# 1_Interface.net
KiCad netlist of a schematic drawn in Altium Designer
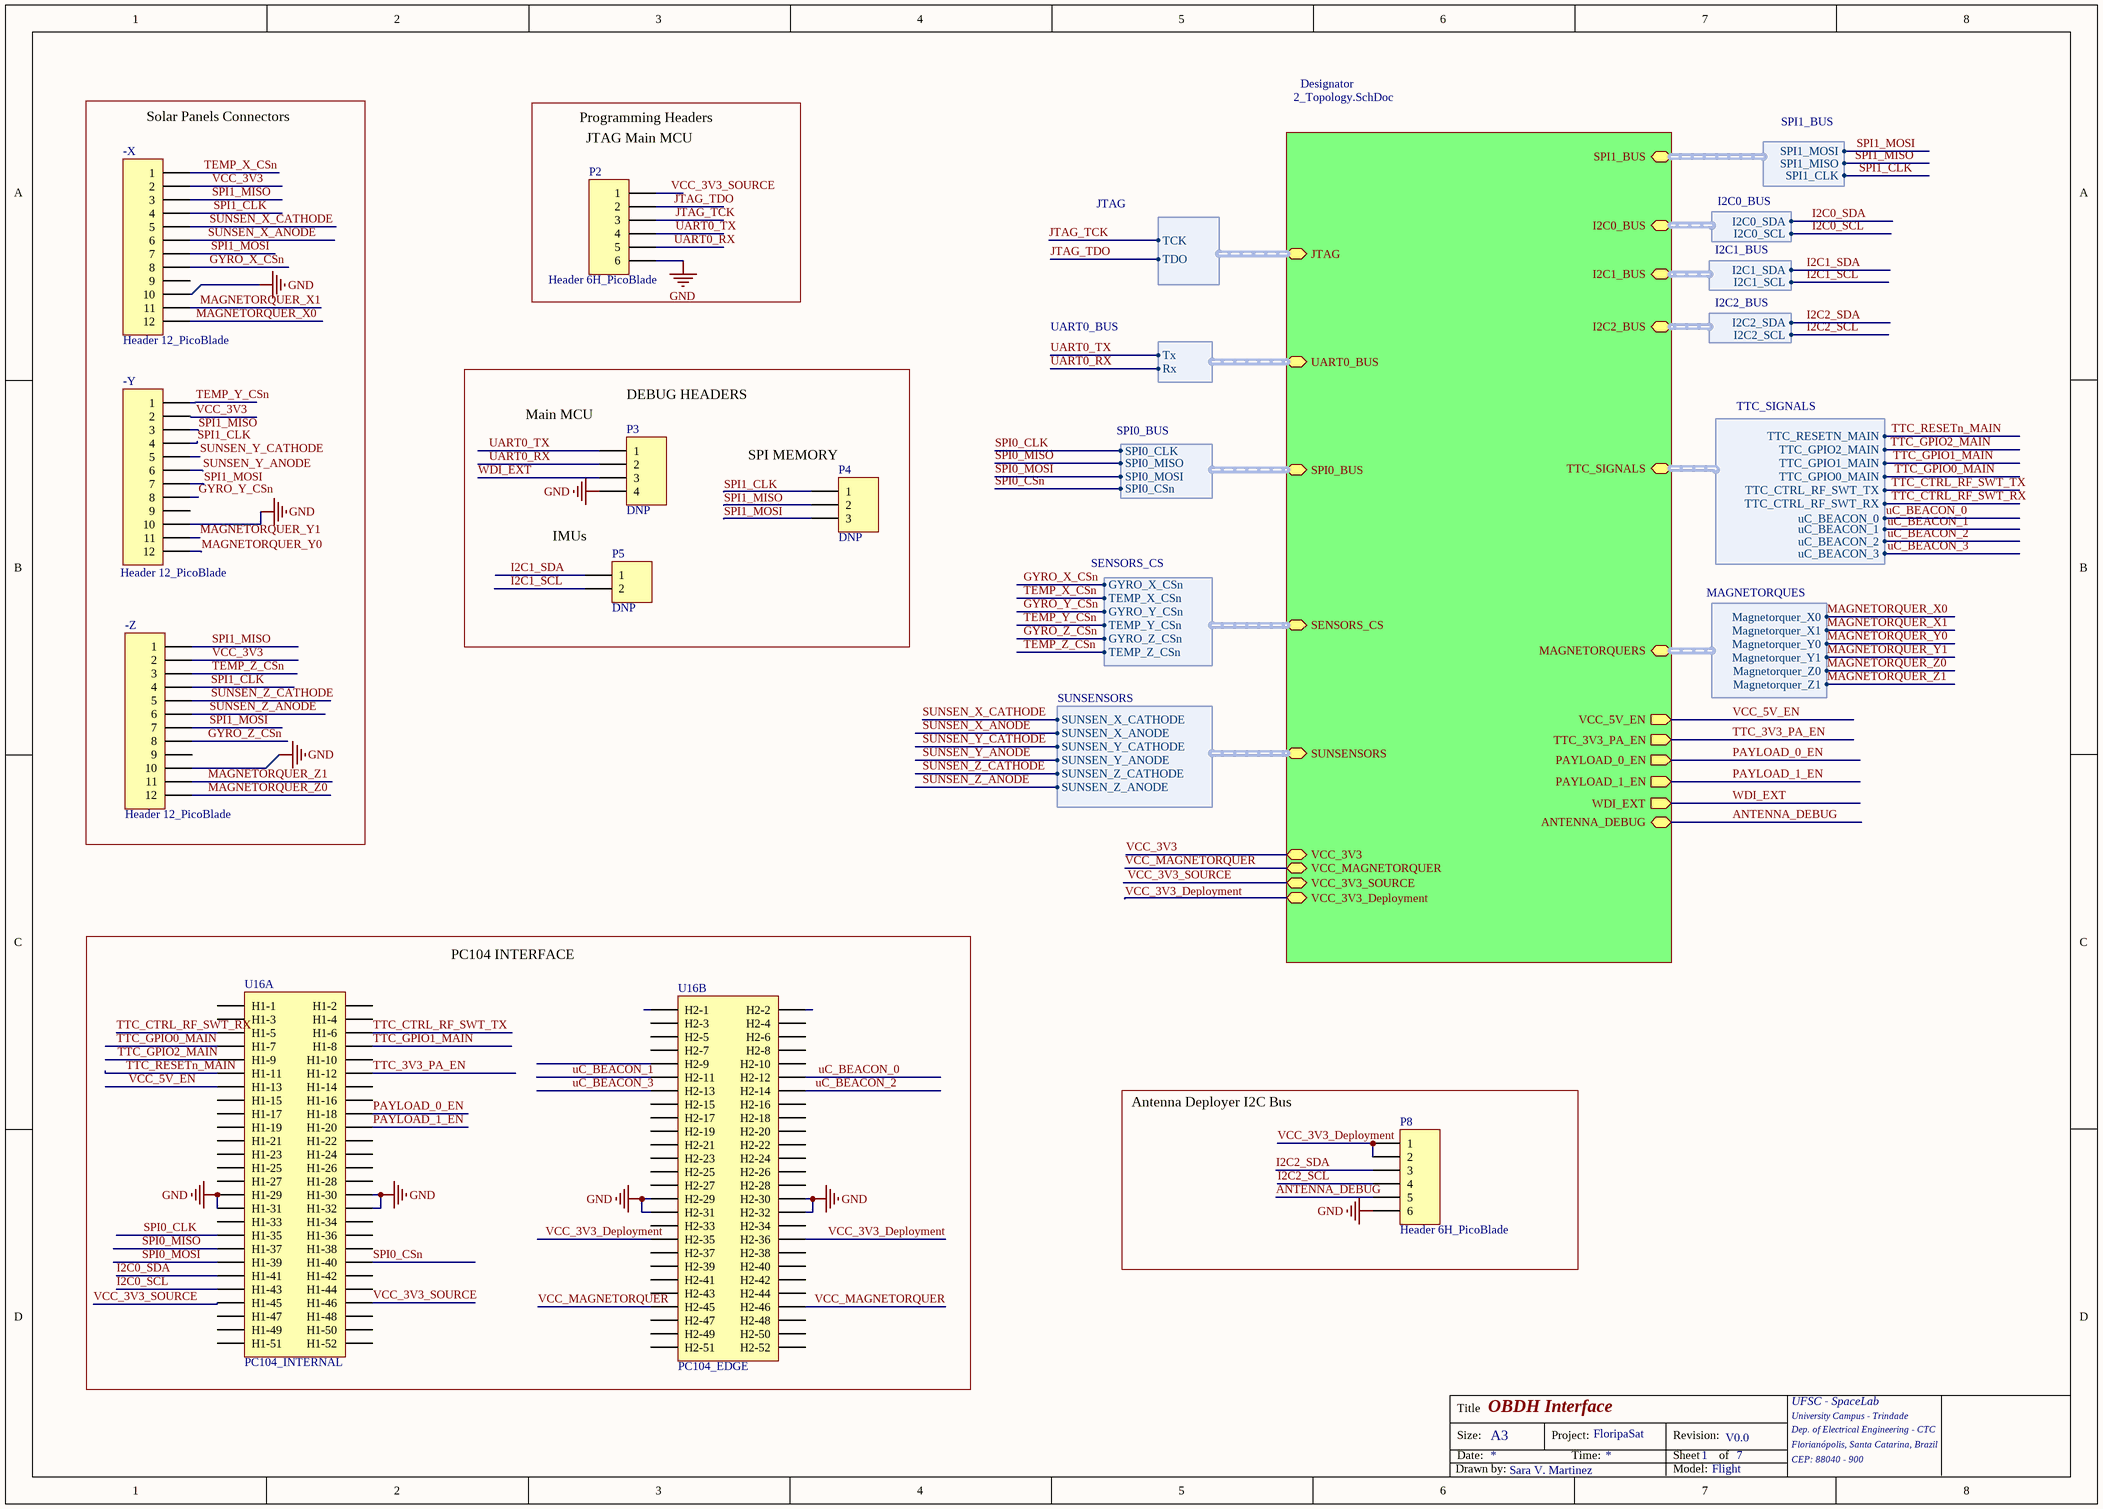
[diagram p0: 1_Interface.SchDoc]

(export (version "E")
  (design (tool "Eeschema 10.0.6"))
  (components
    (comp (ref "-X")
      (value "Header 12_PicoBlade")
      (footprint "HDR12 PicoBlade - duplicate")
      (description "Header, 12-Pin")
      (fields (field (name "PARTNUMBER") "53398-1271") (field (name "PUBLISHER") "Altium Limited"))
      (libsource (lib "FloripaSatSchlib") (part "Header 12_PicoBlade"))
    )
    (comp (ref "-Y")
      (value "Header 12_PicoBlade")
      (footprint "HDR12 PicoBlade - duplicate")
      (description "Header, 12-Pin")
      (fields (field (name "PARTNUMBER") "53398-1271") (field (name "PUBLISHER") "Altium Limited"))
      (libsource (lib "FloripaSatSchlib") (part "Header 12_PicoBlade"))
    )
    (comp (ref "-Z")
      (value "Header 12_PicoBlade")
      (footprint "HDR12 PicoBlade - duplicate")
      (description "Header, 12-Pin")
      (fields (field (name "PARTNUMBER") "533981271") (field (name "PUBLISHER") "Altium Limited"))
      (libsource (lib "FloripaSatSchlib") (part "Header 12_PicoBlade"))
    )
    (comp (ref "P2")
      (value "Header 6H_PicoBlade")
      (footprint "HDR6 PicoBlade")
      (description "Header, 6-Pin, Right Angle")
      (fields (field (name "PARTNUMBER") "53398-0671") (field (name "PUBLISHER") "Altium Limited"))
      (libsource (lib "FloripaSatSchlib") (part "Header 6H_PicoBlade"))
    )
    (comp (ref "P3")
      (value "DNP")
      (footprint "HDR1X4")
      (description "Header, 4-Pin")
      (fields (field (name "PUBLISHER") "Altium Limited"))
      (libsource (lib "Miscellaneous Connectors") (part "Header 4"))
    )
    (comp (ref "P4")
      (value "DNP")
      (footprint "HDR 1X3")
      (description "Header, 3-Pin, Right Angle")
      (fields (field (name "PARTNUMBER") "4-103327-5") (field (name "PUBLISHER") "Altium Limited"))
      (libsource (lib "FloripaSatSchlib") (part "Header 3H"))
    )
    (comp (ref "P5")
      (value "DNP")
      (footprint "HDR1X2H")
      (description "Header, 2-Pin, Right Angle")
      (fields (field (name "PUBLISHER") "Altium Limited"))
      (libsource (lib "Miscellaneous Connectors") (part "Header 2H"))
    )
    (comp (ref "P8")
      (value "Header 6H_PicoBlade")
      (footprint "HDR6 PicoBlade")
      (description "Header, 6-Pin, Right Angle")
      (fields (field (name "PARTNUMBER") "53398-0671") (field (name "PUBLISHER") "Altium Limited"))
      (libsource (lib "") (part "Header 6H_PicoBlade_1"))
    )
    (comp (ref "U16")
      (value "PC104_INTERNAL")
      (footprint "PC104")
      (description "PC104")
      (fields (field (name "PARTNUMBER") "ESQ-126-39-G-D"))
      (libsource (lib "") (part "PC104_1"))
    )
  )
  (nets
    (net (code "13") (name "/ANTENNA_DEBUG") (class "Default")
      (node (ref "P8") (pin "5") (pinfunction "5_5") (pintype "passive"))
    )
    (net (code "14") (name "/GYRO_X_CSn") (class "Default")
      (node (ref "-X") (pin "8") (pinfunction "8_8") (pintype "passive"))
    )
    (net (code "15") (name "/GYRO_Y_CSn") (class "Default")
      (node (ref "-Y") (pin "8") (pinfunction "8_8") (pintype "passive"))
    )
    (net (code "16") (name "/GYRO_Z_CSn") (class "Default")
      (node (ref "-Z") (pin "8") (pinfunction "8_8") (pintype "passive"))
    )
    (net (code "17") (name "/I2C0_SCL") (class "Default")
      (node (ref "U16") (pin "H1-43") (pinfunction "H1-43_H1-43") (pintype "passive"))
    )
    (net (code "18") (name "/I2C0_SDA") (class "Default")
      (node (ref "U16") (pin "H1-41") (pinfunction "H1-41_H1-41") (pintype "passive"))
    )
    (net (code "19") (name "/I2C1_SCL") (class "Default")
      (node (ref "P5") (pin "2") (pinfunction "2_2") (pintype "passive"))
    )
    (net (code "20") (name "/I2C1_SDA") (class "Default")
      (node (ref "P5") (pin "1") (pinfunction "1_1") (pintype "passive"))
    )
    (net (code "21") (name "/I2C2_SCL") (class "Default")
      (node (ref "P8") (pin "4") (pinfunction "4_4") (pintype "passive"))
    )
    (net (code "22") (name "/I2C2_SDA") (class "Default")
      (node (ref "P8") (pin "3") (pinfunction "3_3") (pintype "passive"))
    )
    (net (code "23") (name "/JTAG_TCK") (class "Default")
      (node (ref "P2") (pin "3") (pinfunction "3_3") (pintype "passive"))
    )
    (net (code "24") (name "/JTAG_TDO") (class "Default")
      (node (ref "P2") (pin "2") (pinfunction "2_2") (pintype "passive"))
    )
    (net (code "25") (name "/MAGNETORQUER_X0") (class "Default")
      (node (ref "-X") (pin "12") (pinfunction "12_12") (pintype "passive"))
    )
    (net (code "26") (name "/MAGNETORQUER_X1") (class "Default")
      (node (ref "-X") (pin "11") (pinfunction "11_11") (pintype "passive"))
    )
    (net (code "27") (name "/MAGNETORQUER_Y0") (class "Default")
      (node (ref "-Y") (pin "12") (pinfunction "12_12") (pintype "passive"))
    )
    (net (code "28") (name "/MAGNETORQUER_Y1") (class "Default")
      (node (ref "-Y") (pin "11") (pinfunction "11_11") (pintype "passive"))
    )
    (net (code "29") (name "/MAGNETORQUER_Z0") (class "Default")
      (node (ref "-Z") (pin "12") (pinfunction "12_12") (pintype "passive"))
    )
    (net (code "30") (name "/MAGNETORQUER_Z1") (class "Default")
      (node (ref "-Z") (pin "11") (pinfunction "11_11") (pintype "passive"))
    )
    (net (code "31") (name "/PAYLOAD_0_EN") (class "Default")
      (node (ref "U16") (pin "H1-18") (pinfunction "H1-18_H1-18") (pintype "passive"))
    )
    (net (code "32") (name "/PAYLOAD_1_EN") (class "Default")
      (node (ref "U16") (pin "H1-20") (pinfunction "H1-20_H1-20") (pintype "passive"))
    )
    (net (code "33") (name "/SPI0_CLK") (class "Default")
      (node (ref "U16") (pin "H1-35") (pinfunction "H1-35_H1-35") (pintype "passive"))
    )
    (net (code "34") (name "/SPI0_CSn") (class "Default")
      (node (ref "U16") (pin "H1-40") (pinfunction "H1-40_H1-40") (pintype "passive"))
    )
    (net (code "35") (name "/SPI0_MISO") (class "Default")
      (node (ref "U16") (pin "H1-37") (pinfunction "H1-37_H1-37") (pintype "passive"))
    )
    (net (code "36") (name "/SPI0_MOSI") (class "Default")
      (node (ref "U16") (pin "H1-39") (pinfunction "H1-39_H1-39") (pintype "passive"))
    )
    (net (code "37") (name "/SPI1_CLK") (class "Default")
      (node (ref "-X") (pin "4") (pinfunction "4_4") (pintype "passive"))
      (node (ref "-Y") (pin "4") (pinfunction "4_4") (pintype "passive"))
      (node (ref "-Z") (pin "4") (pinfunction "4_4") (pintype "passive"))
      (node (ref "P4") (pin "1") (pinfunction "1_1") (pintype "passive"))
    )
    (net (code "38") (name "/SPI1_MISO") (class "Default")
      (node (ref "-X") (pin "3") (pinfunction "3_3") (pintype "passive"))
      (node (ref "-Y") (pin "3") (pinfunction "3_3") (pintype "passive"))
      (node (ref "-Z") (pin "1") (pinfunction "1_1") (pintype "passive"))
      (node (ref "P4") (pin "2") (pinfunction "2_2") (pintype "passive"))
    )
    (net (code "39") (name "/SPI1_MOSI") (class "Default")
      (node (ref "-X") (pin "7") (pinfunction "7_7") (pintype "passive"))
      (node (ref "-Y") (pin "7") (pinfunction "7_7") (pintype "passive"))
      (node (ref "-Z") (pin "7") (pinfunction "7_7") (pintype "passive"))
      (node (ref "P4") (pin "3") (pinfunction "3_3") (pintype "passive"))
    )
    (net (code "40") (name "/SUNSEN_X_ANODE") (class "Default")
      (node (ref "-X") (pin "6") (pinfunction "6_6") (pintype "passive"))
    )
    (net (code "41") (name "/SUNSEN_X_CATHODE") (class "Default")
      (node (ref "-X") (pin "5") (pinfunction "5_5") (pintype "passive"))
    )
    (net (code "42") (name "/SUNSEN_Y_ANODE") (class "Default")
      (node (ref "-Y") (pin "6") (pinfunction "6_6") (pintype "passive"))
    )
    (net (code "43") (name "/SUNSEN_Y_CATHODE") (class "Default")
      (node (ref "-Y") (pin "5") (pinfunction "5_5") (pintype "passive"))
    )
    (net (code "44") (name "/SUNSEN_Z_ANODE") (class "Default")
      (node (ref "-Z") (pin "6") (pinfunction "6_6") (pintype "passive"))
    )
    (net (code "45") (name "/SUNSEN_Z_CATHODE") (class "Default")
      (node (ref "-Z") (pin "5") (pinfunction "5_5") (pintype "passive"))
    )
    (net (code "46") (name "/TEMP_X_CSn") (class "Default")
      (node (ref "-X") (pin "1") (pinfunction "1_1") (pintype "passive"))
    )
    (net (code "47") (name "/TEMP_Y_CSn") (class "Default")
      (node (ref "-Y") (pin "1") (pinfunction "1_1") (pintype "passive"))
    )
    (net (code "48") (name "/TEMP_Z_CSn") (class "Default")
      (node (ref "-Z") (pin "3") (pinfunction "3_3") (pintype "passive"))
    )
    (net (code "49") (name "/TTC_3V3_PA_EN") (class "Default")
      (node (ref "U16") (pin "H1-12") (pinfunction "H1-12_H1-12") (pintype "passive"))
    )
    (net (code "50") (name "/TTC_CTRL_RF_SWT_RX") (class "Default")
      (node (ref "U16") (pin "H1-5") (pinfunction "H1-5_H1-5") (pintype "passive"))
    )
    (net (code "51") (name "/TTC_CTRL_RF_SWT_TX") (class "Default")
      (node (ref "U16") (pin "H1-6") (pinfunction "H1-6_H1-6") (pintype "passive"))
    )
    (net (code "52") (name "/TTC_GPIO0_MAIN") (class "Default")
      (node (ref "U16") (pin "H1-7") (pinfunction "H1-7_H1-7") (pintype "passive"))
    )
    (net (code "53") (name "/TTC_GPIO1_MAIN") (class "Default")
      (node (ref "U16") (pin "H1-8") (pinfunction "H1-8_H1-8") (pintype "passive"))
    )
    (net (code "54") (name "/TTC_GPIO2_MAIN") (class "Default")
      (node (ref "U16") (pin "H1-9") (pinfunction "H1-9_H1-9") (pintype "passive"))
    )
    (net (code "55") (name "/TTC_RESETn_MAIN") (class "Default")
      (node (ref "U16") (pin "H1-11") (pinfunction "H1-11_H1-11") (pintype "passive"))
    )
    (net (code "56") (name "/UART0_RX") (class "Default")
      (node (ref "P2") (pin "5") (pinfunction "5_5") (pintype "passive"))
      (node (ref "P3") (pin "2") (pinfunction "2_2") (pintype "passive"))
    )
    (net (code "57") (name "/UART0_TX") (class "Default")
      (node (ref "P2") (pin "4") (pinfunction "4_4") (pintype "passive"))
      (node (ref "P3") (pin "1") (pinfunction "1_1") (pintype "passive"))
    )
    (net (code "58") (name "/VCC_3V3") (class "Default")
      (node (ref "-X") (pin "2") (pinfunction "2_2") (pintype "passive"))
      (node (ref "-Y") (pin "2") (pinfunction "2_2") (pintype "passive"))
      (node (ref "-Z") (pin "2") (pinfunction "2_2") (pintype "passive"))
    )
    (net (code "59") (name "/VCC_3V3_Deployment") (class "Default")
      (node (ref "P8") (pin "1") (pinfunction "1_1") (pintype "passive"))
      (node (ref "P8") (pin "2") (pinfunction "2_2") (pintype "passive"))
      (node (ref "U16") (pin "H2-35") (pinfunction "H2-35_H2-35") (pintype "passive"))
      (node (ref "U16") (pin "H2-36") (pinfunction "H2-36_H2-36") (pintype "passive"))
    )
    (net (code "60") (name "/VCC_3V3_SOURCE") (class "Default")
      (node (ref "P2") (pin "1") (pinfunction "1_1") (pintype "passive"))
      (node (ref "U16") (pin "H1-45") (pinfunction "H1-45_H1-45") (pintype "passive"))
      (node (ref "U16") (pin "H1-46") (pinfunction "H1-46_H1-46") (pintype "passive"))
    )
    (net (code "61") (name "/VCC_5V_EN") (class "Default")
      (node (ref "U16") (pin "H1-13") (pinfunction "H1-13_H1-13") (pintype "passive"))
    )
    (net (code "62") (name "/VCC_MAGNETORQUER") (class "Default")
      (node (ref "U16") (pin "H2-45") (pinfunction "H2-45_H2-45") (pintype "passive"))
      (node (ref "U16") (pin "H2-46") (pinfunction "H2-46_H2-46") (pintype "passive"))
    )
    (net (code "63") (name "/WDI_EXT") (class "Default")
      (node (ref "P3") (pin "3") (pinfunction "3_3") (pintype "passive"))
    )
    (net (code "64") (name "/uC_BEACON_0") (class "Default")
      (node (ref "U16") (pin "H2-12") (pinfunction "H2-12_H2-12") (pintype "passive"))
    )
    (net (code "65") (name "/uC_BEACON_1") (class "Default")
      (node (ref "U16") (pin "H2-11") (pinfunction "H2-11_H2-11") (pintype "passive"))
    )
    (net (code "66") (name "/uC_BEACON_2") (class "Default")
      (node (ref "U16") (pin "H2-14") (pinfunction "H2-14_H2-14") (pintype "passive"))
    )
    (net (code "67") (name "/uC_BEACON_3") (class "Default")
      (node (ref "U16") (pin "H2-13") (pinfunction "H2-13_H2-13") (pintype "passive"))
    )
    (net (code "79") (name "GND") (class "Default")
      (node (ref "-X") (pin "10") (pinfunction "10_10") (pintype "passive"))
      (node (ref "-Y") (pin "10") (pinfunction "10_10") (pintype "passive"))
      (node (ref "-Z") (pin "10") (pinfunction "10_10") (pintype "passive"))
      (node (ref "P2") (pin "6") (pinfunction "6_6") (pintype "passive"))
      (node (ref "P3") (pin "4") (pinfunction "4_4") (pintype "passive"))
      (node (ref "P8") (pin "6") (pinfunction "6_6") (pintype "passive"))
      (node (ref "U16") (pin "H1-29") (pinfunction "H1-29_H1-29") (pintype "passive"))
      (node (ref "U16") (pin "H1-30") (pinfunction "H1-30_H1-30") (pintype "passive"))
      (node (ref "U16") (pin "H1-31") (pinfunction "H1-31_H1-31") (pintype "passive"))
      (node (ref "U16") (pin "H1-32") (pinfunction "H1-32_H1-32") (pintype "passive"))
      (node (ref "U16") (pin "H2-29") (pinfunction "H2-29_H2-29") (pintype "passive"))
      (node (ref "U16") (pin "H2-30") (pinfunction "H2-30_H2-30") (pintype "passive"))
      (node (ref "U16") (pin "H2-31") (pinfunction "H2-31_H2-31") (pintype "passive"))
      (node (ref "U16") (pin "H2-32") (pinfunction "H2-32_H2-32") (pintype "passive"))
    )
    (net (code "80") (name "unconnected-(-X-Pad9)") (class "Default")
      (node (ref "-X") (pin "9") (pinfunction "9_9") (pintype "passive"))
    )
    (net (code "81") (name "unconnected-(-Y-Pad9)") (class "Default")
      (node (ref "-Y") (pin "9") (pinfunction "9_9") (pintype "passive"))
    )
    (net (code "82") (name "unconnected-(-Z-Pad9)") (class "Default")
      (node (ref "-Z") (pin "9") (pinfunction "9_9") (pintype "passive"))
    )
    (net (code "83") (name "unconnected-(U16-PadH1-1)") (class "Default")
      (node (ref "U16") (pin "H1-1") (pinfunction "H1-1_H1-1") (pintype "passive"))
    )
    (net (code "84") (name "unconnected-(U16-PadH1-2)") (class "Default")
      (node (ref "U16") (pin "H1-2") (pinfunction "H1-2_H1-2") (pintype "passive"))
    )
    (net (code "85") (name "unconnected-(U16-PadH1-3)") (class "Default")
      (node (ref "U16") (pin "H1-3") (pinfunction "H1-3_H1-3") (pintype "passive"))
    )
    (net (code "86") (name "unconnected-(U16-PadH1-4)") (class "Default")
      (node (ref "U16") (pin "H1-4") (pinfunction "H1-4_H1-4") (pintype "passive"))
    )
    (net (code "87") (name "unconnected-(U16-PadH1-10)") (class "Default")
      (node (ref "U16") (pin "H1-10") (pinfunction "H1-10_H1-10") (pintype "passive"))
    )
    (net (code "88") (name "unconnected-(U16-PadH1-14)") (class "Default")
      (node (ref "U16") (pin "H1-14") (pinfunction "H1-14_H1-14") (pintype "passive"))
    )
    (net (code "89") (name "unconnected-(U16-PadH1-15)") (class "Default")
      (node (ref "U16") (pin "H1-15") (pinfunction "H1-15_H1-15") (pintype "passive"))
    )
    (net (code "90") (name "unconnected-(U16-PadH1-16)") (class "Default")
      (node (ref "U16") (pin "H1-16") (pinfunction "H1-16_H1-16") (pintype "passive"))
    )
    (net (code "91") (name "unconnected-(U16-PadH1-17)") (class "Default")
      (node (ref "U16") (pin "H1-17") (pinfunction "H1-17_H1-17") (pintype "passive"))
    )
    (net (code "92") (name "unconnected-(U16-PadH1-19)") (class "Default")
      (node (ref "U16") (pin "H1-19") (pinfunction "H1-19_H1-19") (pintype "passive"))
    )
    (net (code "93") (name "unconnected-(U16-PadH1-21)") (class "Default")
      (node (ref "U16") (pin "H1-21") (pinfunction "H1-21_H1-21") (pintype "passive"))
    )
    (net (code "94") (name "unconnected-(U16-PadH1-22)") (class "Default")
      (node (ref "U16") (pin "H1-22") (pinfunction "H1-22_H1-22") (pintype "passive"))
    )
    (net (code "95") (name "unconnected-(U16-PadH1-23)") (class "Default")
      (node (ref "U16") (pin "H1-23") (pinfunction "H1-23_H1-23") (pintype "passive"))
    )
    (net (code "96") (name "unconnected-(U16-PadH1-24)") (class "Default")
      (node (ref "U16") (pin "H1-24") (pinfunction "H1-24_H1-24") (pintype "passive"))
    )
    (net (code "97") (name "unconnected-(U16-PadH1-25)") (class "Default")
      (node (ref "U16") (pin "H1-25") (pinfunction "H1-25_H1-25") (pintype "passive"))
    )
    (net (code "98") (name "unconnected-(U16-PadH1-26)") (class "Default")
      (node (ref "U16") (pin "H1-26") (pinfunction "H1-26_H1-26") (pintype "passive"))
    )
    (net (code "99") (name "unconnected-(U16-PadH1-27)") (class "Default")
      (node (ref "U16") (pin "H1-27") (pinfunction "H1-27_H1-27") (pintype "passive"))
    )
    (net (code "100") (name "unconnected-(U16-PadH1-28)") (class "Default")
      (node (ref "U16") (pin "H1-28") (pinfunction "H1-28_H1-28") (pintype "passive"))
    )
    (net (code "101") (name "unconnected-(U16-PadH1-33)") (class "Default")
      (node (ref "U16") (pin "H1-33") (pinfunction "H1-33_H1-33") (pintype "passive"))
    )
    (net (code "102") (name "unconnected-(U16-PadH1-34)") (class "Default")
      (node (ref "U16") (pin "H1-34") (pinfunction "H1-34_H1-34") (pintype "passive"))
    )
    (net (code "103") (name "unconnected-(U16-PadH1-36)") (class "Default")
      (node (ref "U16") (pin "H1-36") (pinfunction "H1-36_H1-36") (pintype "passive"))
    )
    (net (code "104") (name "unconnected-(U16-PadH1-38)") (class "Default")
      (node (ref "U16") (pin "H1-38") (pinfunction "H1-38_H1-38") (pintype "passive"))
    )
    (net (code "105") (name "unconnected-(U16-PadH1-42)") (class "Default")
      (node (ref "U16") (pin "H1-42") (pinfunction "H1-42_H1-42") (pintype "passive"))
    )
    (net (code "106") (name "unconnected-(U16-PadH1-44)") (class "Default")
      (node (ref "U16") (pin "H1-44") (pinfunction "H1-44_H1-44") (pintype "passive"))
    )
    (net (code "107") (name "unconnected-(U16-PadH1-47)") (class "Default")
      (node (ref "U16") (pin "H1-47") (pinfunction "H1-47_H1-47") (pintype "passive"))
    )
    (net (code "108") (name "unconnected-(U16-PadH1-48)") (class "Default")
      (node (ref "U16") (pin "H1-48") (pinfunction "H1-48_H1-48") (pintype "passive"))
    )
    (net (code "109") (name "unconnected-(U16-PadH1-49)") (class "Default")
      (node (ref "U16") (pin "H1-49") (pinfunction "H1-49_H1-49") (pintype "passive"))
    )
    (net (code "110") (name "unconnected-(U16-PadH1-50)") (class "Default")
      (node (ref "U16") (pin "H1-50") (pinfunction "H1-50_H1-50") (pintype "passive"))
    )
    (net (code "111") (name "unconnected-(U16-PadH1-51)") (class "Default")
      (node (ref "U16") (pin "H1-51") (pinfunction "H1-51_H1-51") (pintype "passive"))
    )
    (net (code "112") (name "unconnected-(U16-PadH1-52)") (class "Default")
      (node (ref "U16") (pin "H1-52") (pinfunction "H1-52_H1-52") (pintype "passive"))
    )
    (net (code "113") (name "unconnected-(U16-PadH2-1)") (class "Default")
      (node (ref "U16") (pin "H2-1") (pinfunction "H2-1_H2-1") (pintype "passive"))
    )
    (net (code "114") (name "unconnected-(U16-PadH2-2)") (class "Default")
      (node (ref "U16") (pin "H2-2") (pinfunction "H2-2_H2-2") (pintype "passive"))
    )
    (net (code "115") (name "unconnected-(U16-PadH2-3)") (class "Default")
      (node (ref "U16") (pin "H2-3") (pinfunction "H2-3_H2-3") (pintype "passive"))
    )
    (net (code "116") (name "unconnected-(U16-PadH2-4)") (class "Default")
      (node (ref "U16") (pin "H2-4") (pinfunction "H2-4_H2-4") (pintype "passive"))
    )
    (net (code "117") (name "unconnected-(U16-PadH2-5)") (class "Default")
      (node (ref "U16") (pin "H2-5") (pinfunction "H2-5_H2-5") (pintype "passive"))
    )
    (net (code "118") (name "unconnected-(U16-PadH2-6)") (class "Default")
      (node (ref "U16") (pin "H2-6") (pinfunction "H2-6_H2-6") (pintype "passive"))
    )
    (net (code "119") (name "unconnected-(U16-PadH2-7)") (class "Default")
      (node (ref "U16") (pin "H2-7") (pinfunction "H2-7_H2-7") (pintype "passive"))
    )
    (net (code "120") (name "unconnected-(U16-PadH2-8)") (class "Default")
      (node (ref "U16") (pin "H2-8") (pinfunction "H2-8_H2-8") (pintype "passive"))
    )
    (net (code "121") (name "unconnected-(U16-PadH2-9)") (class "Default")
      (node (ref "U16") (pin "H2-9") (pinfunction "H2-9_H2-9") (pintype "passive"))
    )
    (net (code "122") (name "unconnected-(U16-PadH2-10)") (class "Default")
      (node (ref "U16") (pin "H2-10") (pinfunction "H2-10_H2-10") (pintype "passive"))
    )
    (net (code "123") (name "unconnected-(U16-PadH2-15)") (class "Default")
      (node (ref "U16") (pin "H2-15") (pinfunction "H2-15_H2-15") (pintype "passive"))
    )
    (net (code "124") (name "unconnected-(U16-PadH2-16)") (class "Default")
      (node (ref "U16") (pin "H2-16") (pinfunction "H2-16_H2-16") (pintype "passive"))
    )
    (net (code "125") (name "unconnected-(U16-PadH2-17)") (class "Default")
      (node (ref "U16") (pin "H2-17") (pinfunction "H2-17_H2-17") (pintype "passive"))
    )
    (net (code "126") (name "unconnected-(U16-PadH2-18)") (class "Default")
      (node (ref "U16") (pin "H2-18") (pinfunction "H2-18_H2-18") (pintype "passive"))
    )
    (net (code "127") (name "unconnected-(U16-PadH2-19)") (class "Default")
      (node (ref "U16") (pin "H2-19") (pinfunction "H2-19_H2-19") (pintype "passive"))
    )
    (net (code "128") (name "unconnected-(U16-PadH2-20)") (class "Default")
      (node (ref "U16") (pin "H2-20") (pinfunction "H2-20_H2-20") (pintype "passive"))
    )
    (net (code "129") (name "unconnected-(U16-PadH2-21)") (class "Default")
      (node (ref "U16") (pin "H2-21") (pinfunction "H2-21_H2-21") (pintype "passive"))
    )
    (net (code "130") (name "unconnected-(U16-PadH2-22)") (class "Default")
      (node (ref "U16") (pin "H2-22") (pinfunction "H2-22_H2-22") (pintype "passive"))
    )
    (net (code "131") (name "unconnected-(U16-PadH2-23)") (class "Default")
      (node (ref "U16") (pin "H2-23") (pinfunction "H2-23_H2-23") (pintype "passive"))
    )
    (net (code "132") (name "unconnected-(U16-PadH2-24)") (class "Default")
      (node (ref "U16") (pin "H2-24") (pinfunction "H2-24_H2-24") (pintype "passive"))
    )
    (net (code "133") (name "unconnected-(U16-PadH2-25)") (class "Default")
      (node (ref "U16") (pin "H2-25") (pinfunction "H2-25_H2-25") (pintype "passive"))
    )
    (net (code "134") (name "unconnected-(U16-PadH2-26)") (class "Default")
      (node (ref "U16") (pin "H2-26") (pinfunction "H2-26_H2-26") (pintype "passive"))
    )
    (net (code "135") (name "unconnected-(U16-PadH2-27)") (class "Default")
      (node (ref "U16") (pin "H2-27") (pinfunction "H2-27_H2-27") (pintype "passive"))
    )
    (net (code "136") (name "unconnected-(U16-PadH2-28)") (class "Default")
      (node (ref "U16") (pin "H2-28") (pinfunction "H2-28_H2-28") (pintype "passive"))
    )
    (net (code "137") (name "unconnected-(U16-PadH2-33)") (class "Default")
      (node (ref "U16") (pin "H2-33") (pinfunction "H2-33_H2-33") (pintype "passive"))
    )
    (net (code "138") (name "unconnected-(U16-PadH2-34)") (class "Default")
      (node (ref "U16") (pin "H2-34") (pinfunction "H2-34_H2-34") (pintype "passive"))
    )
    (net (code "139") (name "unconnected-(U16-PadH2-37)") (class "Default")
      (node (ref "U16") (pin "H2-37") (pinfunction "H2-37_H2-37") (pintype "passive"))
    )
    (net (code "140") (name "unconnected-(U16-PadH2-38)") (class "Default")
      (node (ref "U16") (pin "H2-38") (pinfunction "H2-38_H2-38") (pintype "passive"))
    )
    (net (code "141") (name "unconnected-(U16-PadH2-39)") (class "Default")
      (node (ref "U16") (pin "H2-39") (pinfunction "H2-39_H2-39") (pintype "passive"))
    )
    (net (code "142") (name "unconnected-(U16-PadH2-40)") (class "Default")
      (node (ref "U16") (pin "H2-40") (pinfunction "H2-40_H2-40") (pintype "passive"))
    )
    (net (code "143") (name "unconnected-(U16-PadH2-41)") (class "Default")
      (node (ref "U16") (pin "H2-41") (pinfunction "H2-41_H2-41") (pintype "passive"))
    )
    (net (code "144") (name "unconnected-(U16-PadH2-42)") (class "Default")
      (node (ref "U16") (pin "H2-42") (pinfunction "H2-42_H2-42") (pintype "passive"))
    )
    (net (code "145") (name "unconnected-(U16-PadH2-43)") (class "Default")
      (node (ref "U16") (pin "H2-43") (pinfunction "H2-43_H2-43") (pintype "passive"))
    )
    (net (code "146") (name "unconnected-(U16-PadH2-44)") (class "Default")
      (node (ref "U16") (pin "H2-44") (pinfunction "H2-44_H2-44") (pintype "passive"))
    )
    (net (code "147") (name "unconnected-(U16-PadH2-47)") (class "Default")
      (node (ref "U16") (pin "H2-47") (pinfunction "H2-47_H2-47") (pintype "passive"))
    )
    (net (code "148") (name "unconnected-(U16-PadH2-48)") (class "Default")
      (node (ref "U16") (pin "H2-48") (pinfunction "H2-48_H2-48") (pintype "passive"))
    )
    (net (code "149") (name "unconnected-(U16-PadH2-49)") (class "Default")
      (node (ref "U16") (pin "H2-49") (pinfunction "H2-49_H2-49") (pintype "passive"))
    )
    (net (code "150") (name "unconnected-(U16-PadH2-50)") (class "Default")
      (node (ref "U16") (pin "H2-50") (pinfunction "H2-50_H2-50") (pintype "passive"))
    )
    (net (code "151") (name "unconnected-(U16-PadH2-51)") (class "Default")
      (node (ref "U16") (pin "H2-51") (pinfunction "H2-51_H2-51") (pintype "passive"))
    )
    (net (code "152") (name "unconnected-(U16-PadH2-52)") (class "Default")
      (node (ref "U16") (pin "H2-52") (pinfunction "H2-52_H2-52") (pintype "passive"))
    )
  )
)
